# 07_-_RS232.net
KiCad netlist of a schematic drawn in Altium Designer
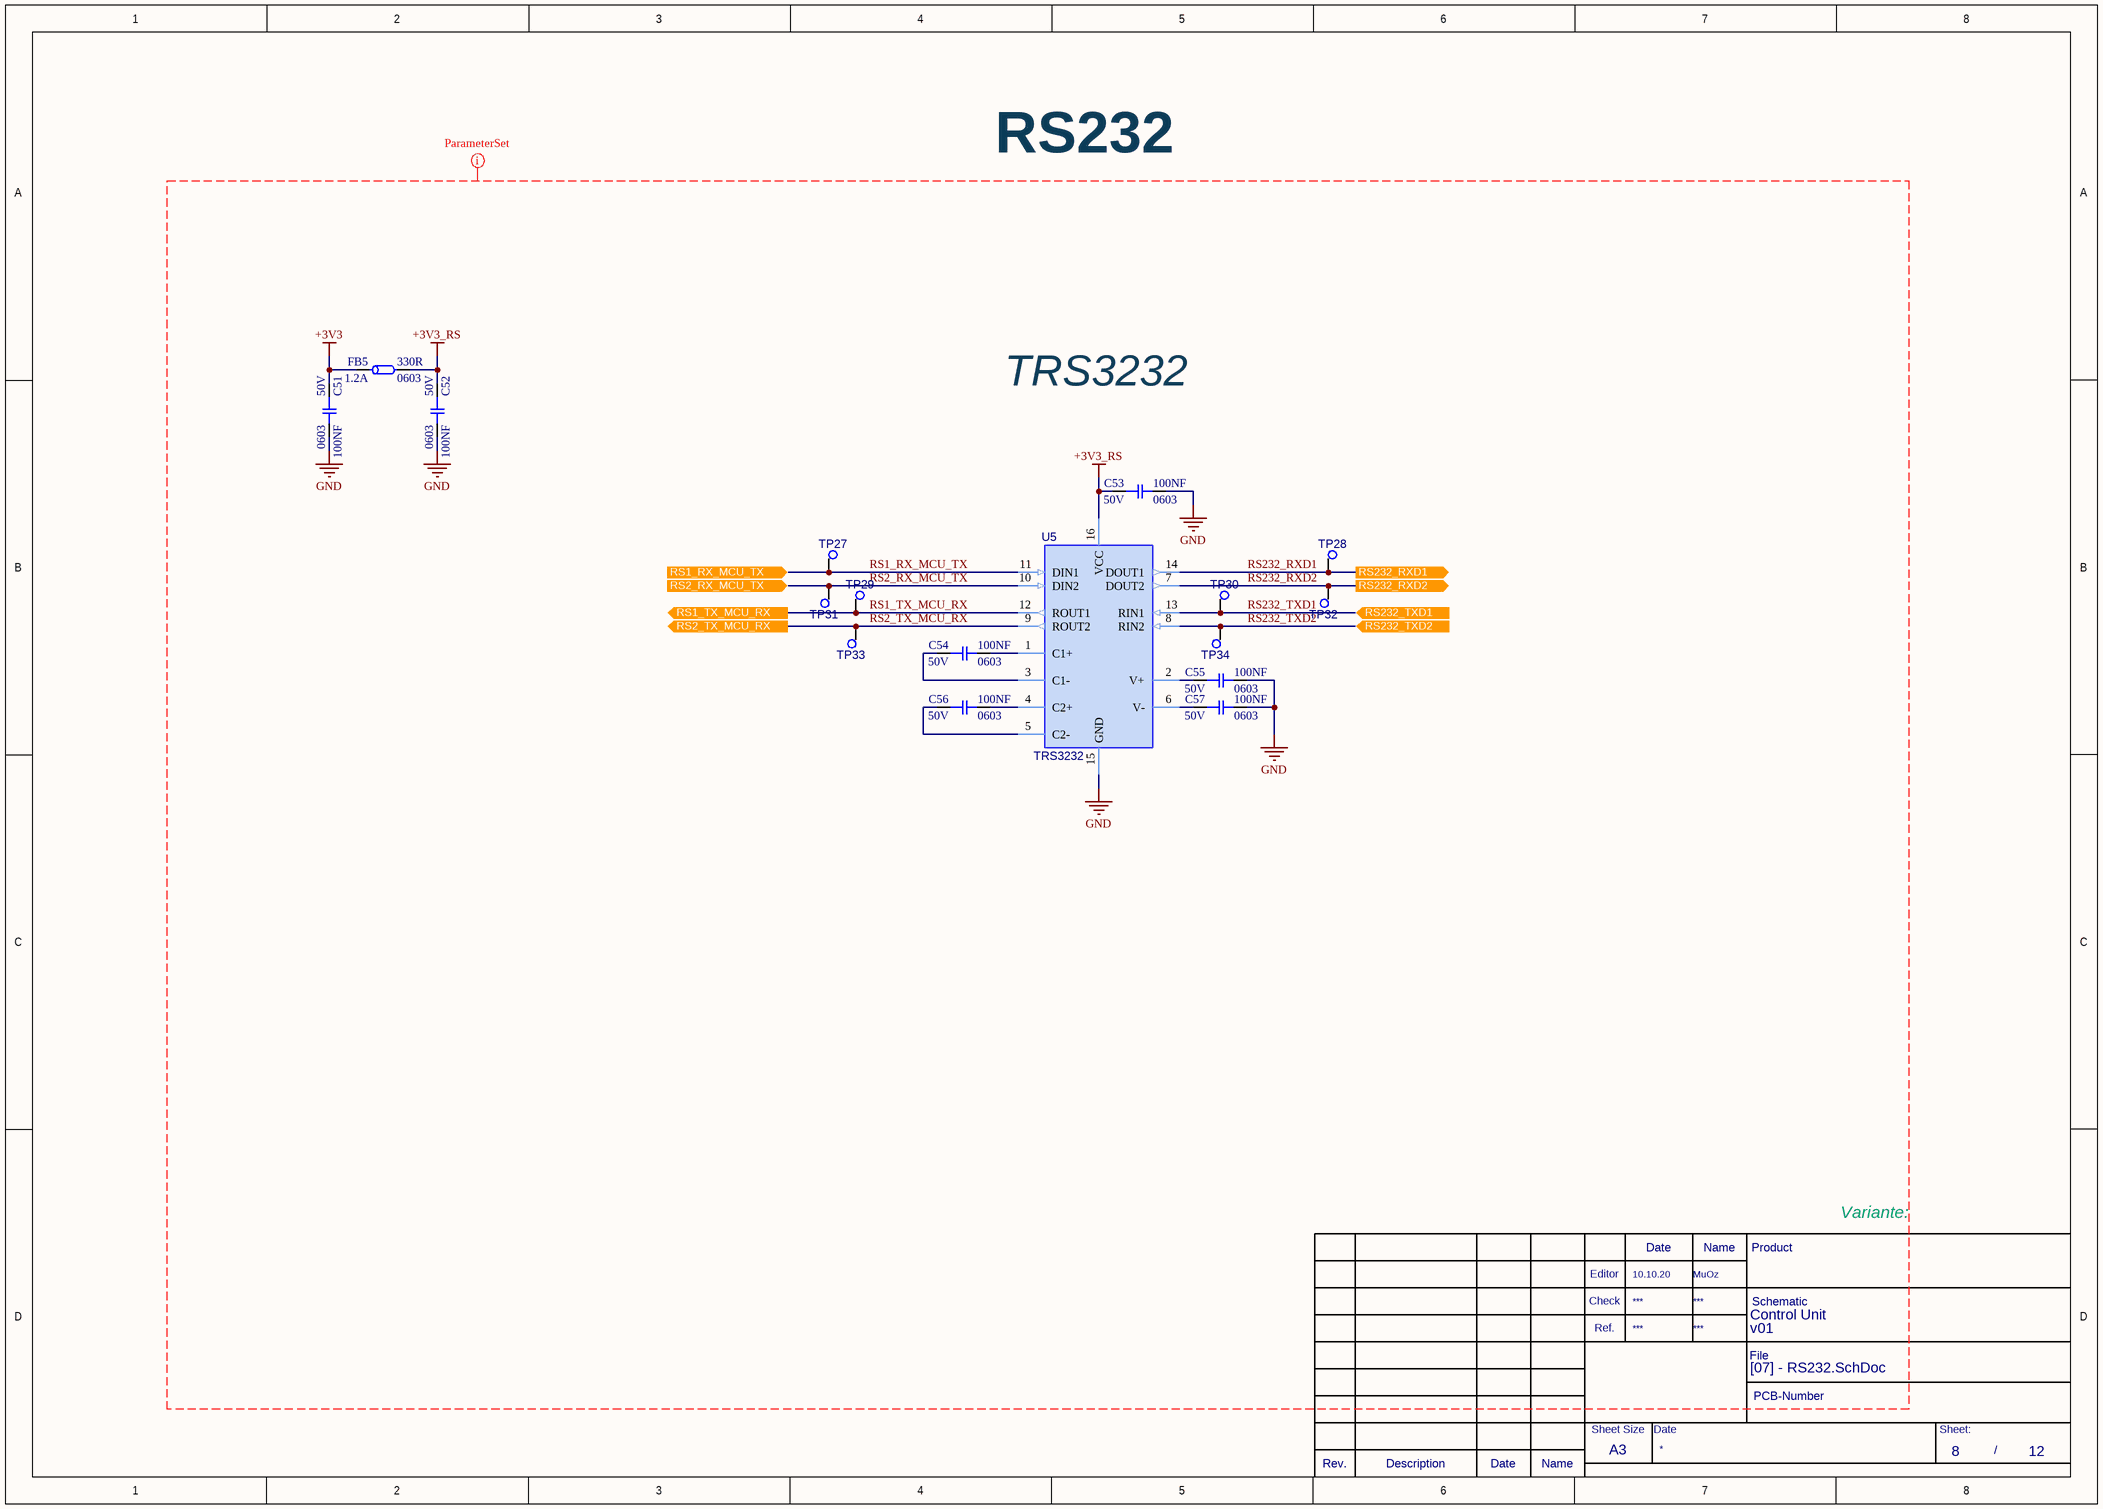
[diagram p0: [07] - RS232.SchDoc]

(export (version "E")
  (design (tool "Eeschema 10.0.6"))
  (components
    (comp (ref "C51")
      (value "100NF")
      (footprint "C-0603")
      (description "CAP CER 0.1UF 50V X7R 0603")
      (fields
        (field (name "MANUFACTURER") "TDK")
        (field (name "MANUFACTURER PART NUMBER") "C1608X7R1H104K080AA")
        (field (name "VOLTAGE RATING") "50V")
        (field (name "CASE CODE (IMPERIAL)") "0603")
        (field (name ".CREATOR") "F:TALI")
      )
      (libsource (lib "BARKO_SCHLIB") (part "C-100NF-0603"))
    )
    (comp (ref "C52")
      (value "100NF")
      (footprint "C-0603")
      (description "CAP CER 0.1UF 50V X7R 0603")
      (fields
        (field (name "MANUFACTURER") "TDK")
        (field (name "MANUFACTURER PART NUMBER") "C1608X7R1H104K080AA")
        (field (name "VOLTAGE RATING") "50V")
        (field (name "CASE CODE (IMPERIAL)") "0603")
        (field (name ".CREATOR") "F:TALI")
      )
      (libsource (lib "BARKO_SCHLIB") (part "C-100NF-0603"))
    )
    (comp (ref "C53")
      (value "100NF")
      (footprint "C-0603")
      (description "CAP CER 0.1UF 50V X7R 0603")
      (fields
        (field (name "MANUFACTURER") "TDK")
        (field (name "MANUFACTURER PART NUMBER") "C1608X7R1H104K080AA")
        (field (name "VOLTAGE RATING") "50V")
        (field (name "CASE CODE (IMPERIAL)") "0603")
        (field (name ".CREATOR") "F:TALI")
      )
      (libsource (lib "BARKO_SCHLIB") (part "C-100NF-0603"))
    )
    (comp (ref "C54")
      (value "100NF")
      (footprint "C-0603")
      (description "CAP CER 0.1UF 50V X7R 0603")
      (fields
        (field (name "MANUFACTURER") "TDK")
        (field (name "MANUFACTURER PART NUMBER") "C1608X7R1H104K080AA")
        (field (name "VOLTAGE RATING") "50V")
        (field (name "CASE CODE (IMPERIAL)") "0603")
        (field (name ".CREATOR") "F:TALI")
      )
      (libsource (lib "BARKO_SCHLIB") (part "C-100NF-0603"))
    )
    (comp (ref "C55")
      (value "100NF")
      (footprint "C-0603")
      (description "CAP CER 0.1UF 50V X7R 0603")
      (fields
        (field (name "MANUFACTURER") "TDK")
        (field (name "MANUFACTURER PART NUMBER") "C1608X7R1H104K080AA")
        (field (name "VOLTAGE RATING") "50V")
        (field (name "CASE CODE (IMPERIAL)") "0603")
        (field (name ".CREATOR") "F:TALI")
      )
      (libsource (lib "BARKO_SCHLIB") (part "C-100NF-0603"))
    )
    (comp (ref "C56")
      (value "100NF")
      (footprint "C-0603")
      (description "CAP CER 0.1UF 50V X7R 0603")
      (fields
        (field (name "MANUFACTURER") "TDK")
        (field (name "MANUFACTURER PART NUMBER") "C1608X7R1H104K080AA")
        (field (name "VOLTAGE RATING") "50V")
        (field (name "CASE CODE (IMPERIAL)") "0603")
        (field (name ".CREATOR") "F:TALI")
      )
      (libsource (lib "BARKO_SCHLIB") (part "C-100NF-0603"))
    )
    (comp (ref "C57")
      (value "100NF")
      (footprint "C-0603")
      (description "CAP CER 0.1UF 50V X7R 0603")
      (fields
        (field (name "MANUFACTURER") "TDK")
        (field (name "MANUFACTURER PART NUMBER") "C1608X7R1H104K080AA")
        (field (name "VOLTAGE RATING") "50V")
        (field (name "CASE CODE (IMPERIAL)") "0603")
        (field (name ".CREATOR") "F:TALI")
      )
      (libsource (lib "BARKO_SCHLIB") (part "C-100NF-0603"))
    )
    (comp (ref "FB5")
      (value "330R")
      (footprint "FB-0603")
      (description "FERRITE BEAD 330 OHM 0603 1LN")
      (fields
        (field (name "MANUFACTURER") "Murata")
        (field (name "MANUFACTURER PART NUMBER") "BLM18PG331SN1D")
        (field (name "CASE/PACKAGE") "0603")
        (field (name "DC CURRENT") "1.2A")
        (field (name ".CREATOR") "M.OZKAN")
      )
      (libsource (lib "BARKO_SCHLIB") (part "FB-330R-0603"))
    )
    (comp (ref "TP27")
      (value "MECH-TESTPOINT")
      (footprint "MECH-TESTPOINT")
      (fields (field (name ".CREATOR") "F:TALI"))
      (libsource (lib "BARKO_SCHLIB") (part "MECH-TESTPOINT"))
    )
    (comp (ref "TP28")
      (value "MECH-TESTPOINT")
      (footprint "MECH-TESTPOINT")
      (fields (field (name ".CREATOR") "F:TALI"))
      (libsource (lib "BARKO_SCHLIB") (part "MECH-TESTPOINT"))
    )
    (comp (ref "TP29")
      (value "MECH-TESTPOINT")
      (footprint "MECH-TESTPOINT")
      (fields (field (name ".CREATOR") "F:TALI"))
      (libsource (lib "BARKO_SCHLIB") (part "MECH-TESTPOINT"))
    )
    (comp (ref "TP30")
      (value "MECH-TESTPOINT")
      (footprint "MECH-TESTPOINT")
      (fields (field (name ".CREATOR") "F:TALI"))
      (libsource (lib "BARKO_SCHLIB") (part "MECH-TESTPOINT"))
    )
    (comp (ref "TP31")
      (value "MECH-TESTPOINT")
      (footprint "MECH-TESTPOINT")
      (fields (field (name ".CREATOR") "F:TALI"))
      (libsource (lib "BARKO_SCHLIB") (part "MECH-TESTPOINT"))
    )
    (comp (ref "TP32")
      (value "MECH-TESTPOINT")
      (footprint "MECH-TESTPOINT")
      (fields (field (name ".CREATOR") "F:TALI"))
      (libsource (lib "BARKO_SCHLIB") (part "MECH-TESTPOINT"))
    )
    (comp (ref "TP33")
      (value "MECH-TESTPOINT")
      (footprint "MECH-TESTPOINT")
      (fields (field (name ".CREATOR") "F:TALI"))
      (libsource (lib "BARKO_SCHLIB") (part "MECH-TESTPOINT"))
    )
    (comp (ref "TP34")
      (value "MECH-TESTPOINT")
      (footprint "MECH-TESTPOINT")
      (fields (field (name ".CREATOR") "F:TALI"))
      (libsource (lib "BARKO_SCHLIB") (part "MECH-TESTPOINT"))
    )
    (comp (ref "U5")
      (value "TRS3232")
      (footprint "TSSOP16")
      (description "IC TRANSCEIVER FULL 2/2 16TSSOP")
      (libsource (lib "SCHLIB") (part "IC-TRS3232ECPWR"))
    )
  )
  (nets
    (net (code "1") (name "+3V3") (class "Default")
      (node (ref "C51") (pin "1") (pinfunction "1_1") (pintype "passive"))
      (node (ref "FB5") (pin "1") (pinfunction "1_1") (pintype "passive"))
    )
    (net (code "2") (name "+3V3_RS") (class "Default")
      (node (ref "C52") (pin "1") (pinfunction "1_1") (pintype "passive"))
      (node (ref "C53") (pin "1") (pinfunction "1_1") (pintype "passive"))
      (node (ref "FB5") (pin "2") (pinfunction "2_2") (pintype "passive"))
      (node (ref "U5") (pin "16") (pinfunction "VCC_16") (pintype "power_in"))
    )
    (net (code "3") (name "/RS1_RX_MCU_TX") (class "Default")
      (node (ref "TP27") (pin "1") (pinfunction "1_1") (pintype "passive"))
      (node (ref "U5") (pin "11") (pinfunction "DIN1_11") (pintype "input"))
    )
    (net (code "4") (name "/RS1_TX_MCU_RX") (class "Default")
      (node (ref "TP29") (pin "1") (pinfunction "1_1") (pintype "passive"))
      (node (ref "U5") (pin "12") (pinfunction "ROUT1_12") (pintype "output"))
    )
    (net (code "5") (name "/RS2_RX_MCU_TX") (class "Default")
      (node (ref "TP31") (pin "1") (pinfunction "1_1") (pintype "passive"))
      (node (ref "U5") (pin "10") (pinfunction "DIN2_10") (pintype "input"))
    )
    (net (code "6") (name "/RS2_TX_MCU_RX") (class "Default")
      (node (ref "TP33") (pin "1") (pinfunction "1_1") (pintype "passive"))
      (node (ref "U5") (pin "9") (pinfunction "ROUT2_9") (pintype "output"))
    )
    (net (code "7") (name "/RS232_RXD1") (class "Default")
      (node (ref "TP28") (pin "1") (pinfunction "1_1") (pintype "passive"))
      (node (ref "U5") (pin "14") (pinfunction "DOUT1_14") (pintype "output"))
    )
    (net (code "8") (name "/RS232_RXD2") (class "Default")
      (node (ref "TP32") (pin "1") (pinfunction "1_1") (pintype "passive"))
      (node (ref "U5") (pin "7") (pinfunction "DOUT2_7") (pintype "output"))
    )
    (net (code "9") (name "/RS232_TXD1") (class "Default")
      (node (ref "TP30") (pin "1") (pinfunction "1_1") (pintype "passive"))
      (node (ref "U5") (pin "13") (pinfunction "RIN1_13") (pintype "input"))
    )
    (net (code "10") (name "/RS232_TXD2") (class "Default")
      (node (ref "TP34") (pin "1") (pinfunction "1_1") (pintype "passive"))
      (node (ref "U5") (pin "8") (pinfunction "RIN2_8") (pintype "input"))
    )
    (net (code "11") (name "GND") (class "Default")
      (node (ref "C51") (pin "2") (pinfunction "2_2") (pintype "passive"))
      (node (ref "C52") (pin "2") (pinfunction "2_2") (pintype "passive"))
      (node (ref "C53") (pin "2") (pinfunction "2_2") (pintype "passive"))
      (node (ref "C55") (pin "2") (pinfunction "2_2") (pintype "passive"))
      (node (ref "C57") (pin "2") (pinfunction "2_2") (pintype "passive"))
      (node (ref "U5") (pin "15") (pinfunction "GND_15") (pintype "power_in"))
    )
    (net (code "12") (name "Net-(U5-C1+)") (class "Default")
      (node (ref "C54") (pin "2") (pinfunction "2_2") (pintype "passive"))
      (node (ref "U5") (pin "1") (pinfunction "C1+_1") (pintype "passive"))
    )
    (net (code "13") (name "Net-(U5-C1-)") (class "Default")
      (node (ref "C54") (pin "1") (pinfunction "1_1") (pintype "passive"))
      (node (ref "U5") (pin "3") (pinfunction "C1-_3") (pintype "passive"))
    )
    (net (code "14") (name "Net-(U5-C2+)") (class "Default")
      (node (ref "C56") (pin "2") (pinfunction "2_2") (pintype "passive"))
      (node (ref "U5") (pin "4") (pinfunction "C2+_4") (pintype "passive"))
    )
    (net (code "15") (name "Net-(U5-C2-)") (class "Default")
      (node (ref "C56") (pin "1") (pinfunction "1_1") (pintype "passive"))
      (node (ref "U5") (pin "5") (pinfunction "C2-_5") (pintype "passive"))
    )
    (net (code "16") (name "Net-(U5-V+)") (class "Default")
      (node (ref "C55") (pin "1") (pinfunction "1_1") (pintype "passive"))
      (node (ref "U5") (pin "2") (pinfunction "V+_2") (pintype "passive"))
    )
    (net (code "17") (name "Net-(U5-V-)") (class "Default")
      (node (ref "C57") (pin "1") (pinfunction "1_1") (pintype "passive"))
      (node (ref "U5") (pin "6") (pinfunction "V-_6") (pintype "passive"))
    )
  )
)
